# BatteryMonitor.net
KiCad netlist of a schematic drawn in Altium Designer
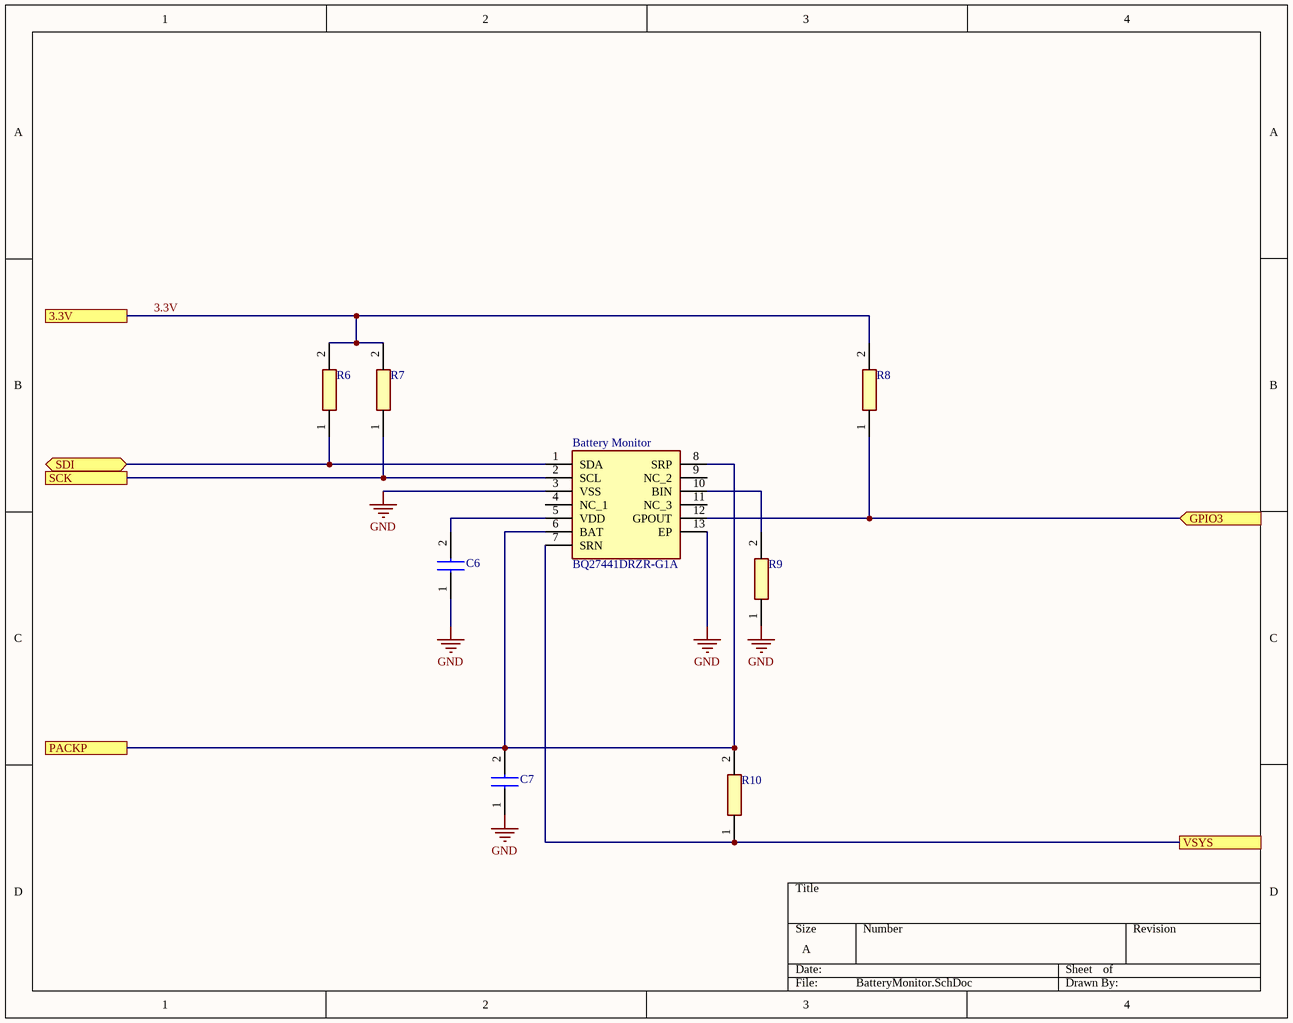
[diagram p0: BatteryMonitor.SchDoc]

(export (version "E")
  (design (tool "Eeschema 10.0.6"))
  (components
    (comp (ref "Battery Monitor")
      (value "BQ27441DRZR-G1A")
      (footprint "SamacSys:BQ27441DRZRG1A")
      (description "Integrated Circuit")
      (fields (field (name "MOUSER2 PART NUMBER") "595-BQ27441DRZR-G1A"))
      (libsource (lib "*") (part "BQ27441DRZR-G1A"))
    )
    (comp (ref "C6")
      (value "C0603C150K5GAC")
      (footprint "SamacSys:CAPC1608X87N")
      (description "Capacitor")
      (fields (field (name "MOUSER PART NUMBER") "80-C0603C150K5GAC"))
      (libsource (lib "*") (part "C0603C150K5GAC"))
    )
    (comp (ref "C7")
      (value "C0603C150K5GAC")
      (footprint "SamacSys:CAPC1608X87N")
      (description "Capacitor")
      (fields (field (name "MOUSER PART NUMBER") "80-C0603C150K5GAC"))
      (libsource (lib "*") (part "C0603C150K5GAC"))
    )
    (comp (ref "R6")
      (value "CRCW06034K70JNEA")
      (footprint "SamacSys:RESC1608X50N")
      (description "Resistor")
      (fields (field (name "MOUSER PART NUMBER") "71-CRCW0603J-4.7K-E3"))
      (libsource (lib "*") (part "CRCW06034K70JNEA"))
    )
    (comp (ref "R7")
      (value "CRCW06034K70JNEA")
      (footprint "SamacSys:RESC1608X50N")
      (description "Resistor")
      (fields (field (name "MOUSER PART NUMBER") "71-CRCW0603J-4.7K-E3"))
      (libsource (lib "*") (part "CRCW06034K70JNEA"))
    )
    (comp (ref "R8")
      (value "CRCW06034K70JNEA")
      (footprint "SamacSys:RESC1608X50N")
      (description "Resistor")
      (fields (field (name "MOUSER PART NUMBER") "71-CRCW0603J-4.7K-E3"))
      (libsource (lib "*") (part "CRCW06034K70JNEA"))
    )
    (comp (ref "R9")
      (value "CRCW06034K70JNEA")
      (footprint "SamacSys:RESC1608X50N")
      (description "Resistor")
      (fields (field (name "MOUSER PART NUMBER") "71-CRCW0603J-4.7K-E3"))
      (libsource (lib "*") (part "CRCW06034K70JNEA"))
    )
    (comp (ref "R10")
      (value "CRCW06034K70JNEA")
      (footprint "SamacSys:RESC1608X50N")
      (description "Resistor")
      (fields (field (name "MOUSER PART NUMBER") "71-CRCW0603J-4.7K-E3"))
      (libsource (lib "*") (part "CRCW06034K70JNEA"))
    )
  )
  (nets
    (net (code "1") (name "/3.3V") (class "Default")
      (node (ref "R6") (pin "2") (pinfunction "2_2") (pintype "passive"))
      (node (ref "R7") (pin "2") (pinfunction "2_2") (pintype "passive"))
      (node (ref "R8") (pin "2") (pinfunction "2_2") (pintype "passive"))
    )
    (net (code "2") (name "/GPIO3") (class "Default")
      (node (ref "Battery Monitor") (pin "12") (pinfunction "GPOUT_12") (pintype "passive"))
      (node (ref "R8") (pin "1") (pinfunction "1_1") (pintype "passive"))
    )
    (net (code "3") (name "/PACKP") (class "Default")
      (node (ref "Battery Monitor") (pin "6") (pinfunction "BAT_6") (pintype "passive"))
      (node (ref "Battery Monitor") (pin "8") (pinfunction "SRP_8") (pintype "passive"))
      (node (ref "C7") (pin "2") (pinfunction "2_2") (pintype "passive"))
      (node (ref "R10") (pin "2") (pinfunction "2_2") (pintype "passive"))
    )
    (net (code "4") (name "/SCK") (class "Default")
      (node (ref "Battery Monitor") (pin "2") (pinfunction "SCL_2") (pintype "passive"))
      (node (ref "R7") (pin "1") (pinfunction "1_1") (pintype "passive"))
    )
    (net (code "5") (name "/SDI") (class "Default")
      (node (ref "Battery Monitor") (pin "1") (pinfunction "SDA_1") (pintype "passive"))
      (node (ref "R6") (pin "1") (pinfunction "1_1") (pintype "passive"))
    )
    (net (code "6") (name "/VSYS") (class "Default")
      (node (ref "Battery Monitor") (pin "7") (pinfunction "SRN_7") (pintype "passive"))
      (node (ref "R10") (pin "1") (pinfunction "1_1") (pintype "passive"))
    )
    (net (code "7") (name "GND") (class "Default")
      (node (ref "Battery Monitor") (pin "13") (pinfunction "EP_13") (pintype "passive"))
      (node (ref "Battery Monitor") (pin "3") (pinfunction "VSS_3") (pintype "passive"))
      (node (ref "C6") (pin "1") (pinfunction "1_1") (pintype "passive"))
      (node (ref "C7") (pin "1") (pinfunction "1_1") (pintype "passive"))
      (node (ref "R9") (pin "1") (pinfunction "1_1") (pintype "passive"))
    )
    (net (code "8") (name "Net-(Battery Monitor-BIN)") (class "Default")
      (node (ref "Battery Monitor") (pin "10") (pinfunction "BIN_10") (pintype "passive"))
      (node (ref "R9") (pin "2") (pinfunction "2_2") (pintype "passive"))
    )
    (net (code "9") (name "Net-(Battery Monitor-VDD)") (class "Default")
      (node (ref "Battery Monitor") (pin "5") (pinfunction "VDD_5") (pintype "passive"))
      (node (ref "C6") (pin "2") (pinfunction "2_2") (pintype "passive"))
    )
    (net (code "10") (name "unconnected-(Battery Monitor-NC_1-Pad4)") (class "Default")
      (node (ref "Battery Monitor") (pin "4") (pinfunction "NC_1_4") (pintype "passive"))
    )
    (net (code "11") (name "unconnected-(Battery Monitor-NC_2-Pad9)") (class "Default")
      (node (ref "Battery Monitor") (pin "9") (pinfunction "NC_2_9") (pintype "passive"))
    )
    (net (code "12") (name "unconnected-(Battery Monitor-NC_3-Pad11)") (class "Default")
      (node (ref "Battery Monitor") (pin "11") (pinfunction "NC_3_11") (pintype "passive"))
    )
  )
)
